# LPCB218_-_EXTERNAL_I2C.net
KiCad netlist of a schematic drawn in Altium Designer
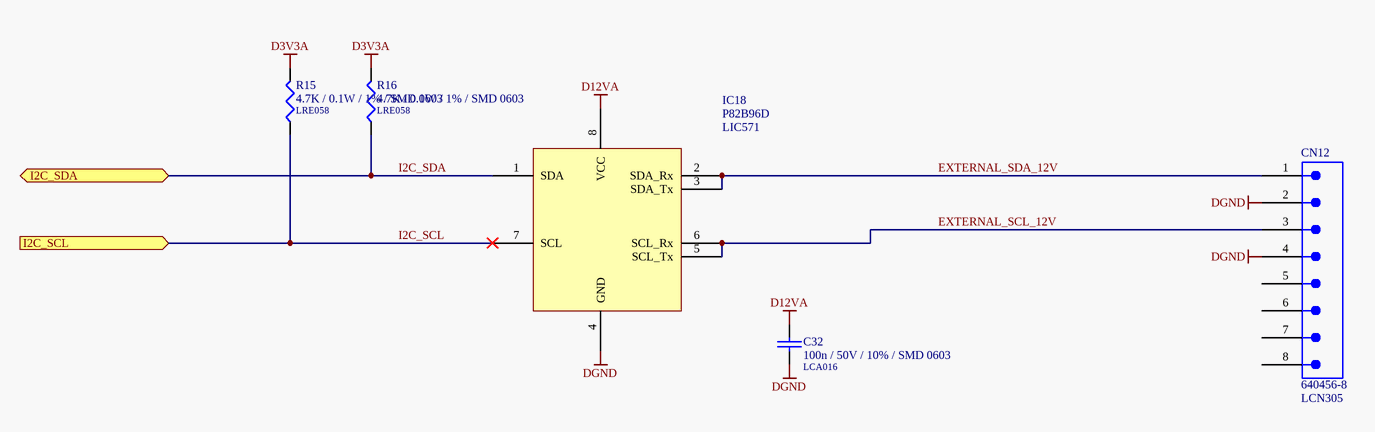
[diagram p0: LPCB218 - EXTERNAL I2C.SchDoc]

(export (version "E")
  (design (tool "Eeschema 10.0.6"))
  (components
    (comp (ref "C32")
      (value "100n / 50V / 10% / SMD 0603")
      (footprint "LFP011__CC1608-0603-IPC7351_B")
      (description "Capacitor, Ceramic Chip, 100nF (0.1uF), 50V, 5%, SMD 0603 [LCA016]")
      (fields (field (name "LDL_NUMBER") "LCA016"))
      (libsource (lib "LDL_Capacitors") (part "100n / 50V / 10% / SMD 0603"))
    )
    (comp (ref "CN12")
      (value "640456-8")
      (footprint "640456-8")
      (description "Connector, Male Header, 8 Way")
      (fields (field (name "LDL_NUMBER") "LCN305"))
      (libsource (lib "LDL_Connectors") (part "640456-8"))
    )
    (comp (ref "IC18")
      (value "P82B96D")
      (footprint "LFP097__SOIC150-8")
      (description "IC, I2C Line Driver [LIC571]")
      (fields (field (name "LDL_NUMBER") "LIC571"))
      (libsource (lib "LDL_Semiconductors") (part "P82B96D"))
    )
    (comp (ref "R15")
      (value "4.7K / 0.1W / 1% / SMD 0603")
      (footprint "LFP020__CR1608-0603-IPC7351_B")
      (description "Resistor, Ceramic Chip, 4K7, 0.1W, 1%, SMD 0603 [LRE058]")
      (fields (field (name "LDL_NUMBER") "LRE058"))
      (libsource (lib "LDL_Resistors") (part "4.7K / 0.1W / 1% / SMD 0603"))
    )
    (comp (ref "R16")
      (value "4.7K / 0.1W / 1% / SMD 0603")
      (footprint "LFP020__CR1608-0603-IPC7351_B")
      (description "Resistor, Ceramic Chip, 4K7, 0.1W, 1%, SMD 0603 [LRE058]")
      (fields (field (name "LDL_NUMBER") "LRE058"))
      (libsource (lib "LDL_Resistors") (part "4.7K / 0.1W / 1% / SMD 0603"))
    )
  )
  (nets
    (net (code "1") (name "/EXTERNAL_SCL_12V") (class "Default")
      (node (ref "CN12") (pin "3") (pinfunction "3_3") (pintype "passive"))
      (node (ref "IC18") (pin "5") (pinfunction "SCL_Tx_5") (pintype "passive"))
      (node (ref "IC18") (pin "6") (pinfunction "SCL_Rx_6") (pintype "passive"))
    )
    (net (code "2") (name "/EXTERNAL_SDA_12V") (class "Default")
      (node (ref "CN12") (pin "1") (pinfunction "1_1") (pintype "passive"))
      (node (ref "IC18") (pin "2") (pinfunction "SDA_Rx_2") (pintype "passive"))
      (node (ref "IC18") (pin "3") (pinfunction "SDA_Tx_3") (pintype "passive"))
    )
    (net (code "3") (name "/I2C_SCL") (class "Default")
      (node (ref "IC18") (pin "7") (pinfunction "SCL_7") (pintype "passive"))
      (node (ref "R15") (pin "1") (pintype "passive"))
    )
    (net (code "4") (name "/I2C_SDA") (class "Default")
      (node (ref "IC18") (pin "1") (pinfunction "SDA_1") (pintype "passive"))
      (node (ref "R16") (pin "1") (pintype "passive"))
    )
    (net (code "5") (name "D3V3A") (class "Default")
      (node (ref "R15") (pin "2") (pintype "passive"))
      (node (ref "R16") (pin "2") (pintype "passive"))
    )
    (net (code "6") (name "D12VA") (class "Default")
      (node (ref "C32") (pin "1") (pintype "passive"))
      (node (ref "IC18") (pin "8") (pinfunction "VCC_8") (pintype "power_in"))
    )
    (net (code "7") (name "DGND") (class "Default")
      (node (ref "C32") (pin "2") (pintype "passive"))
      (node (ref "CN12") (pin "2") (pinfunction "2_2") (pintype "passive"))
      (node (ref "CN12") (pin "4") (pinfunction "4_4") (pintype "passive"))
      (node (ref "IC18") (pin "4") (pinfunction "GND_4") (pintype "power_in"))
    )
    (net (code "8") (name "unconnected-(CN12-Pad5)") (class "Default")
      (node (ref "CN12") (pin "5") (pinfunction "5_5") (pintype "passive"))
    )
    (net (code "9") (name "unconnected-(CN12-Pad6)") (class "Default")
      (node (ref "CN12") (pin "6") (pinfunction "6_6") (pintype "passive"))
    )
    (net (code "10") (name "unconnected-(CN12-Pad7)") (class "Default")
      (node (ref "CN12") (pin "7") (pinfunction "7_7") (pintype "passive"))
    )
    (net (code "11") (name "unconnected-(CN12-Pad8)") (class "Default")
      (node (ref "CN12") (pin "8") (pinfunction "8_8") (pintype "passive"))
    )
  )
)
